# usbcan_20190426.net
KiCad netlist of a schematic drawn in EAGLE
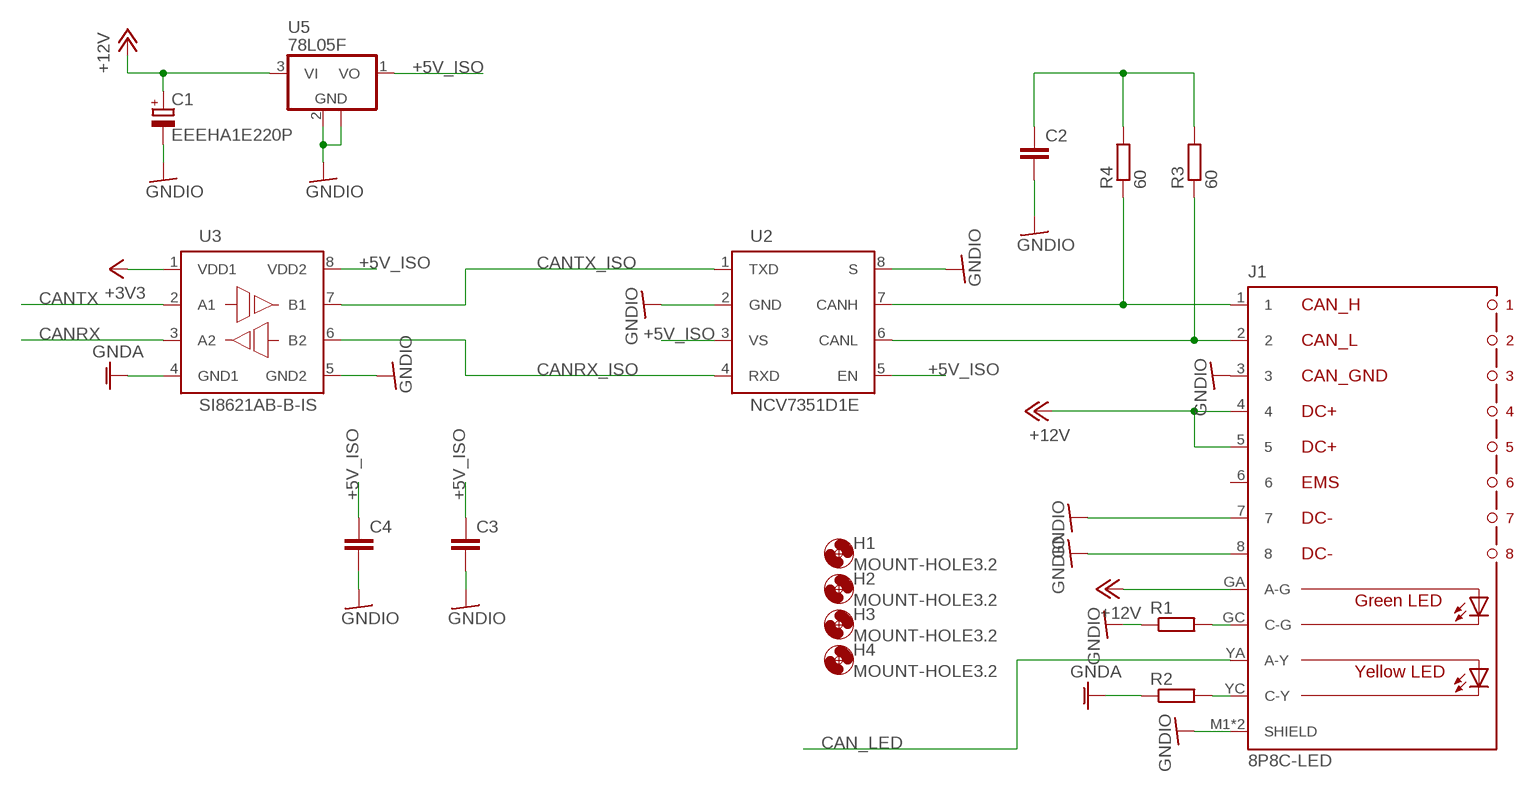
[diagram p0: schematic, sheet 1]
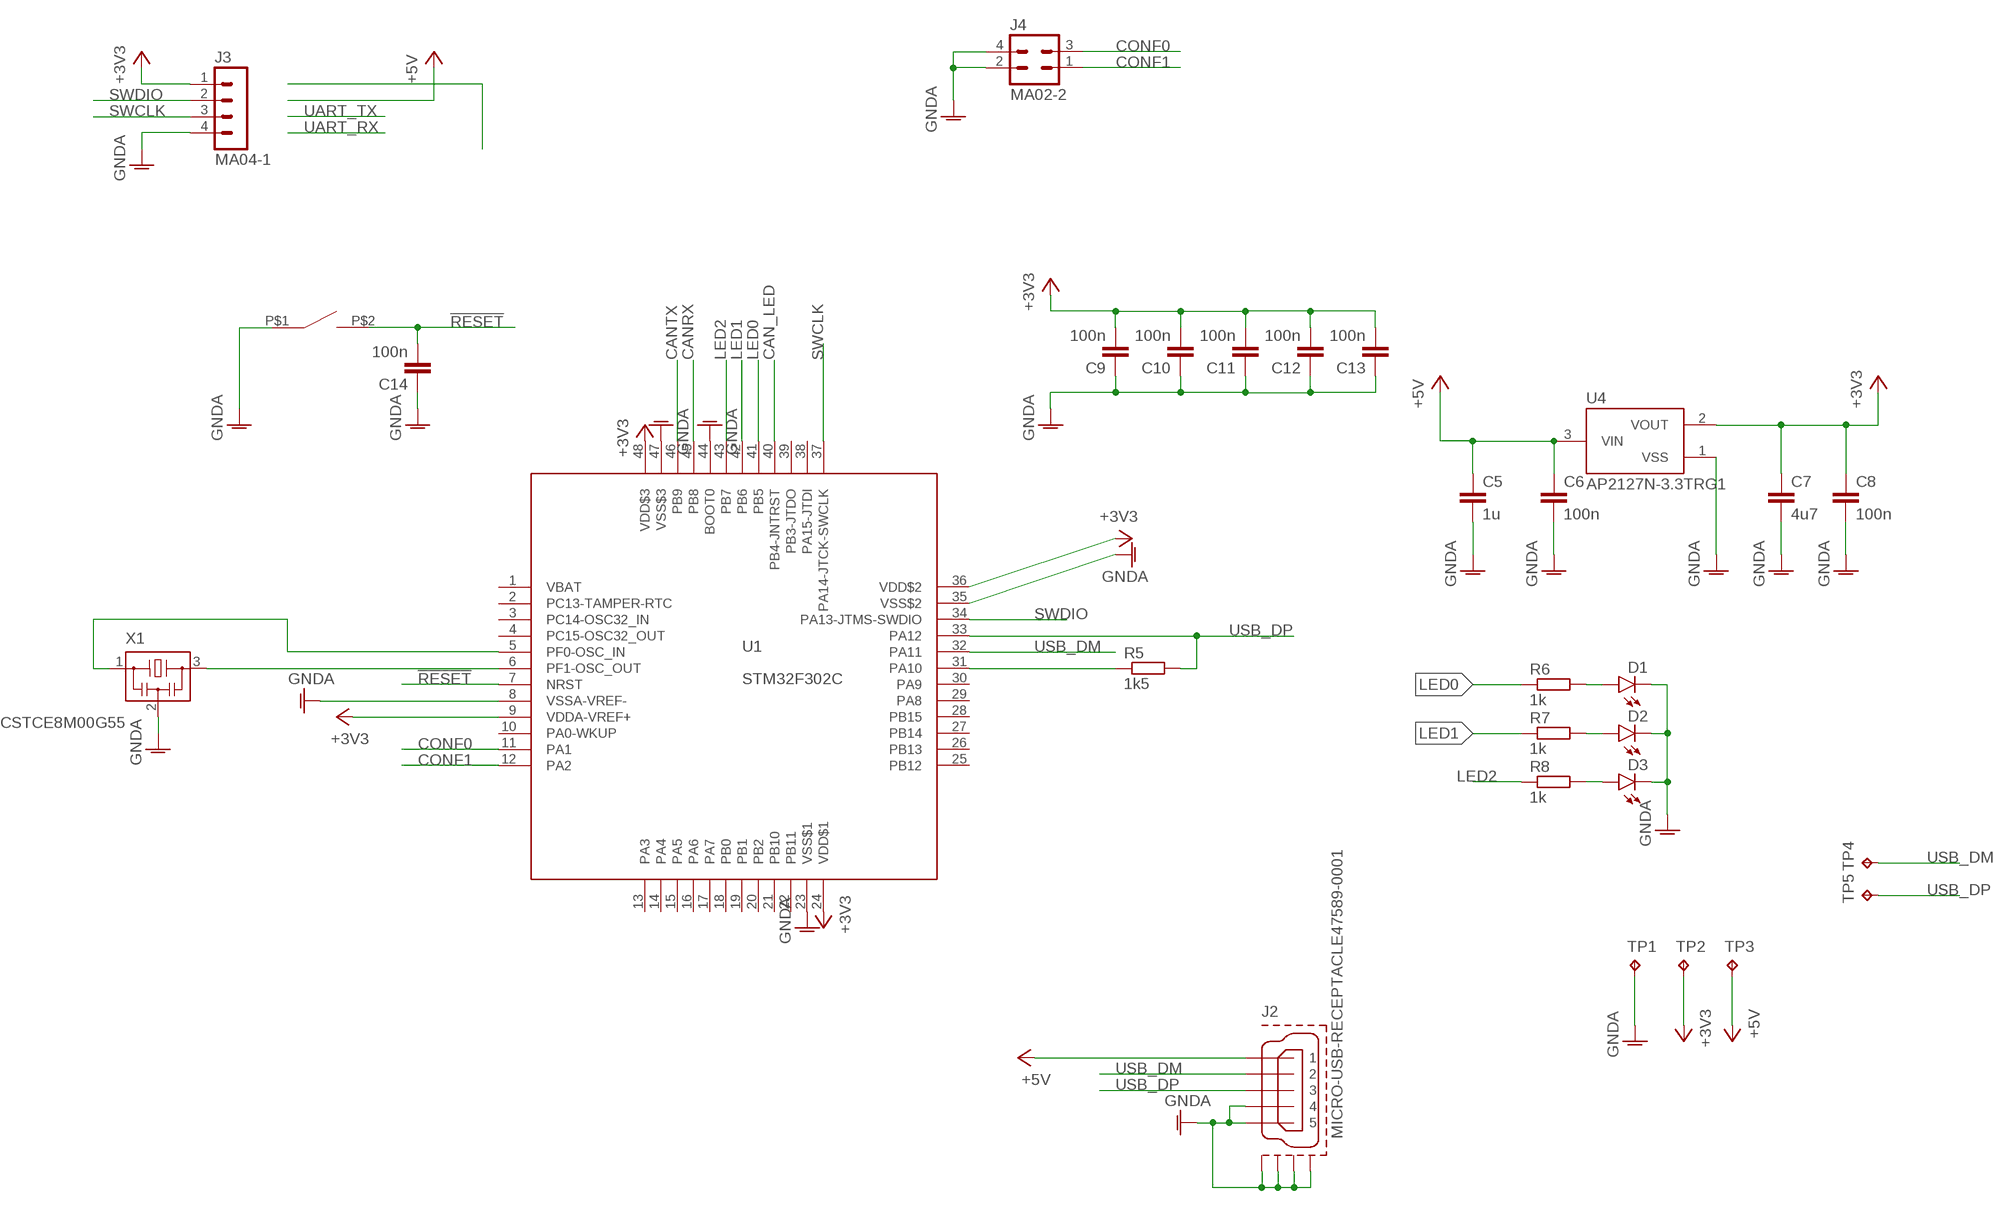
[diagram p1: schematic, sheet 2]

(export (version "E")
  (design (tool "Eeschema 10.0.6"))
  (components
    (comp (ref "C1")
      (value "EEEHA1E220P")
      (footprint "eagle-import:153CLV-0605")
      (libsource (lib "eagle-import") (part "CPOL-EU153CLV-0605"))
    )
    (comp (ref "C2")
      (value "C-EUC0603")
      (footprint "eagle-import:C0603")
      (libsource (lib "eagle-import") (part "rcl_334_C-EUC0603"))
    )
    (comp (ref "C3")
      (value "C-EUC0603")
      (footprint "eagle-import:C0603")
      (libsource (lib "eagle-import") (part "rcl_334_C-EUC0603"))
    )
    (comp (ref "C4")
      (value "C-EUC0603")
      (footprint "eagle-import:C0603")
      (libsource (lib "eagle-import") (part "rcl_334_C-EUC0603"))
    )
    (comp (ref "H1")
      (value "MOUNT-HOLE3.2")
      (footprint "eagle-import:3,2")
      (libsource (lib "eagle-import") (part "MOUNT-HOLE3.2"))
    )
    (comp (ref "H2")
      (value "MOUNT-HOLE3.2")
      (footprint "eagle-import:3,2")
      (libsource (lib "eagle-import") (part "MOUNT-HOLE3.2"))
    )
    (comp (ref "H3")
      (value "MOUNT-HOLE3.2")
      (footprint "eagle-import:3,2")
      (libsource (lib "eagle-import") (part "MOUNT-HOLE3.2"))
    )
    (comp (ref "H4")
      (value "MOUNT-HOLE3.2")
      (footprint "eagle-import:3,2")
      (libsource (lib "eagle-import") (part "MOUNT-HOLE3.2"))
    )
    (comp (ref "J1")
      (value "8P8C-LED")
      (footprint "eagle-import:8P8C-LED")
      (libsource (lib "eagle-import") (part "8P8C-LED"))
    )
    (comp (ref "R1")
      (value "R-EU_R0603")
      (footprint "eagle-import:R0603")
      (libsource (lib "eagle-import") (part "rcl_334_R-EU_R0603"))
    )
    (comp (ref "R2")
      (value "R-EU_R0603")
      (footprint "eagle-import:R0603")
      (libsource (lib "eagle-import") (part "rcl_334_R-EU_R0603"))
    )
    (comp (ref "R3")
      (value "60")
      (footprint "eagle-import:R0603")
      (libsource (lib "eagle-import") (part "rcl_334_R-EU_R0603"))
    )
    (comp (ref "R4")
      (value "60")
      (footprint "eagle-import:R0603")
      (libsource (lib "eagle-import") (part "rcl_334_R-EU_R0603"))
    )
    (comp (ref "U2")
      (value "NCV7351D1E")
      (footprint "eagle-import:SO08")
      (libsource (lib "eagle-import") (part "NCV7351D1E"))
    )
    (comp (ref "U3")
      (value "SI8621AB-B-IS")
      (footprint "eagle-import:SO08")
      (libsource (lib "eagle-import") (part "SI8621AB-B-IS"))
    )
    (comp (ref "U5")
      (value "78L05F")
      (footprint "eagle-import:SOT89")
      (libsource (lib "eagle-import") (part "78LF05"))
    )
    (comp (ref "C5")
      (value "1u")
      (footprint "eagle-import:C0603")
      (libsource (lib "eagle-import") (part "C-EUC0603"))
    )
    (comp (ref "C6")
      (value "100n")
      (footprint "eagle-import:C0603")
      (libsource (lib "eagle-import") (part "C-EUC0603"))
    )
    (comp (ref "C7")
      (value "4u7")
      (footprint "eagle-import:C0805")
      (libsource (lib "eagle-import") (part "C-EUC0805"))
    )
    (comp (ref "C8")
      (value "100n")
      (footprint "eagle-import:C0603")
      (libsource (lib "eagle-import") (part "C-EUC0603"))
    )
    (comp (ref "C9")
      (value "100n")
      (footprint "eagle-import:C0603")
      (libsource (lib "eagle-import") (part "C-EUC0603"))
    )
    (comp (ref "C10")
      (value "100n")
      (footprint "eagle-import:C0603")
      (libsource (lib "eagle-import") (part "C-EUC0603"))
    )
    (comp (ref "C11")
      (value "100n")
      (footprint "eagle-import:C0603")
      (libsource (lib "eagle-import") (part "C-EUC0603"))
    )
    (comp (ref "C12")
      (value "100n")
      (footprint "eagle-import:C0603")
      (libsource (lib "eagle-import") (part "C-EUC0603"))
    )
    (comp (ref "C13")
      (value "100n")
      (footprint "eagle-import:C0603")
      (libsource (lib "eagle-import") (part "C-EUC0603"))
    )
    (comp (ref "C14")
      (value "100n")
      (footprint "eagle-import:C0603")
      (libsource (lib "eagle-import") (part "C-EUC0603"))
    )
    (comp (ref "D1")
      (value "LEDCHIPLED_0805")
      (footprint "eagle-import:CHIPLED_0805")
      (libsource (lib "eagle-import") (part "LEDCHIPLED_0805"))
    )
    (comp (ref "D2")
      (value "LEDCHIPLED_0805")
      (footprint "eagle-import:CHIPLED_0805")
      (libsource (lib "eagle-import") (part "LEDCHIPLED_0805"))
    )
    (comp (ref "D3")
      (value "LEDCHIPLED_0805")
      (footprint "eagle-import:CHIPLED_0805")
      (libsource (lib "eagle-import") (part "LEDCHIPLED_0805"))
    )
    (comp (ref "J2")
      (value "MICRO-USB-RECEPTACLE47589-0001")
      (footprint "eagle-import:47589-0001")
      (libsource (lib "eagle-import") (part "MICRO-USB-RECEPTACLE47589-0001"))
    )
    (comp (ref "J3")
      (value "MA04-1")
      (footprint "eagle-import:MA04-1")
      (libsource (lib "eagle-import") (part "MA04-1"))
    )
    (comp (ref "J4")
      (value "MA02-2")
      (footprint "eagle-import:MA02-2W")
      (libsource (lib "eagle-import") (part "MA02-2"))
    )
    (comp (ref "R5")
      (value "1k5")
      (footprint "eagle-import:R0603")
      (libsource (lib "eagle-import") (part "R-EU_R0603"))
    )
    (comp (ref "R6")
      (value "1k")
      (footprint "eagle-import:R0603")
      (libsource (lib "eagle-import") (part "R-EU_R0603"))
    )
    (comp (ref "R7")
      (value "1k")
      (footprint "eagle-import:R0603")
      (libsource (lib "eagle-import") (part "R-EU_R0603"))
    )
    (comp (ref "R8")
      (value "1k")
      (footprint "eagle-import:R0603")
      (libsource (lib "eagle-import") (part "R-EU_R0603"))
    )
    (comp (ref "S1")
      (value "SWITCH_TACTILETOP")
      (footprint "eagle-import:SWITCH_TACTILE_3X6")
      (libsource (lib "eagle-import") (part "SWITCH_TACTILETOP"))
    )
    (comp (ref "TP1")
      (value "TPB1,27")
      (footprint "eagle-import:B1,27")
      (libsource (lib "eagle-import") (part "TPB1,27"))
    )
    (comp (ref "TP2")
      (value "TPB1,27")
      (footprint "eagle-import:B1,27")
      (libsource (lib "eagle-import") (part "TPB1,27"))
    )
    (comp (ref "TP3")
      (value "TPB1,27")
      (footprint "eagle-import:B1,27")
      (libsource (lib "eagle-import") (part "TPB1,27"))
    )
    (comp (ref "TP4")
      (value "TPB1,27")
      (footprint "eagle-import:B1,27")
      (libsource (lib "eagle-import") (part "TPB1,27"))
    )
    (comp (ref "TP5")
      (value "TPB1,27")
      (footprint "eagle-import:B1,27")
      (libsource (lib "eagle-import") (part "TPB1,27"))
    )
    (comp (ref "U1")
      (value "STM32F302C")
      (footprint "eagle-import:LQFP48")
      (libsource (lib "eagle-import") (part "STM32F303C"))
    )
    (comp (ref "U4")
      (value "AP2127N-3.3TRG1")
      (footprint "eagle-import:SOT95P240X110-3")
      (libsource (lib "eagle-import") (part "XC6206"))
    )
    (comp (ref "X1")
      (value "CSTCE8M00G55")
      (footprint "eagle-import:CSTCE8M00G55")
      (libsource (lib "eagle-import") (part "CSTCE8M00G55"))
    )
  )
  (nets
    (net (code "1") (name "+3V3") (class "Default")
      (node (ref "C10") (pin "2") (pinfunction "2_2") (pintype "passive"))
      (node (ref "C11") (pin "2") (pinfunction "2_2") (pintype "passive"))
      (node (ref "C12") (pin "2") (pinfunction "2_2") (pintype "passive"))
      (node (ref "C13") (pin "2") (pinfunction "2_2") (pintype "passive"))
      (node (ref "C7") (pin "1") (pinfunction "1_1") (pintype "passive"))
      (node (ref "C8") (pin "1") (pinfunction "1_1") (pintype "passive"))
      (node (ref "C9") (pin "2") (pinfunction "2_2") (pintype "passive"))
      (node (ref "J3") (pin "1") (pinfunction "1_1") (pintype "passive"))
      (node (ref "TP2") (pin "TP") (pinfunction "TP_TP") (pintype "input"))
      (node (ref "U1") (pin "24") (pinfunction "VDD$1_24") (pintype "passive"))
      (node (ref "U1") (pin "36") (pinfunction "VDD$2_36") (pintype "passive"))
      (node (ref "U1") (pin "48") (pinfunction "VDD$3_48") (pintype "passive"))
      (node (ref "U1") (pin "9") (pinfunction "VDDA-VREF+_9") (pintype "bidirectional"))
      (node (ref "U3") (pin "1") (pinfunction "VDD1_1") (pintype "power_in"))
      (node (ref "U4") (pin "2") (pinfunction "VOUT_2") (pintype "bidirectional"))
    )
    (net (code "2") (name "+5V") (class "Default")
      (node (ref "C5") (pin "1") (pinfunction "1_1") (pintype "passive"))
      (node (ref "C6") (pin "1") (pinfunction "1_1") (pintype "passive"))
      (node (ref "J2") (pin "1") (pinfunction "1_1") (pintype "input"))
      (node (ref "TP3") (pin "TP") (pinfunction "TP_TP") (pintype "input"))
      (node (ref "U4") (pin "3") (pinfunction "VIN_3") (pintype "bidirectional"))
    )
    (net (code "3") (name "+5V_ISO") (class "Default")
      (node (ref "C3") (pin "1") (pinfunction "1_1") (pintype "passive"))
      (node (ref "C4") (pin "1") (pinfunction "1_1") (pintype "passive"))
      (node (ref "U2") (pin "3") (pinfunction "VS_3") (pintype "power_in"))
      (node (ref "U2") (pin "5") (pinfunction "EN_5") (pintype "input"))
      (node (ref "U3") (pin "8") (pinfunction "VDD2_8") (pintype "power_in"))
      (node (ref "U5") (pin "1") (pinfunction "VO_1") (pintype "passive"))
    )
    (net (code "4") (name "+12V") (class "Default")
      (node (ref "C1") (pin "+") (pinfunction "+_+") (pintype "passive"))
      (node (ref "J1") (pin "4") (pinfunction "4_4") (pintype "input"))
      (node (ref "J1") (pin "5") (pinfunction "5_5") (pintype "input"))
      (node (ref "J1") (pin "GA") (pinfunction "A-G_GA") (pintype "passive"))
      (node (ref "U5") (pin "3") (pinfunction "VI_3") (pintype "input"))
    )
    (net (code "5") (name "CANRX") (class "Default")
      (node (ref "U1") (pin "45") (pinfunction "PB8_45") (pintype "bidirectional"))
      (node (ref "U3") (pin "3") (pinfunction "A2_3") (pintype "output"))
    )
    (net (code "6") (name "CANRX_ISO") (class "Default")
      (node (ref "U2") (pin "4") (pinfunction "RXD_4") (pintype "output"))
      (node (ref "U3") (pin "6") (pinfunction "B2_6") (pintype "output"))
    )
    (net (code "7") (name "CANTX") (class "Default")
      (node (ref "U1") (pin "46") (pinfunction "PB9_46") (pintype "bidirectional"))
      (node (ref "U3") (pin "2") (pinfunction "A1_2") (pintype "input"))
    )
    (net (code "8") (name "CANTX_ISO") (class "Default")
      (node (ref "U2") (pin "1") (pinfunction "TXD_1") (pintype "input"))
      (node (ref "U3") (pin "7") (pinfunction "B1_7") (pintype "output"))
    )
    (net (code "9") (name "CAN_LED") (class "Default")
      (node (ref "J1") (pin "YA") (pinfunction "A-Y_YA") (pintype "passive"))
      (node (ref "U1") (pin "40") (pinfunction "PB4-JNTRST_40") (pintype "bidirectional"))
    )
    (net (code "10") (name "CONF0") (class "Default")
      (node (ref "J4") (pin "3") (pinfunction "3_3") (pintype "passive"))
      (node (ref "U1") (pin "11") (pinfunction "PA1_11") (pintype "bidirectional"))
    )
    (net (code "11") (name "CONF1") (class "Default")
      (node (ref "J4") (pin "1") (pinfunction "1_1") (pintype "passive"))
      (node (ref "U1") (pin "12") (pinfunction "PA2_12") (pintype "bidirectional"))
    )
    (net (code "12") (name "GNDA") (class "Default")
      (node (ref "C10") (pin "1") (pinfunction "1_1") (pintype "passive"))
      (node (ref "C11") (pin "1") (pinfunction "1_1") (pintype "passive"))
      (node (ref "C12") (pin "1") (pinfunction "1_1") (pintype "passive"))
      (node (ref "C13") (pin "1") (pinfunction "1_1") (pintype "passive"))
      (node (ref "C14") (pin "1") (pinfunction "1_1") (pintype "passive"))
      (node (ref "C5") (pin "2") (pinfunction "2_2") (pintype "passive"))
      (node (ref "C6") (pin "2") (pinfunction "2_2") (pintype "passive"))
      (node (ref "C7") (pin "2") (pinfunction "2_2") (pintype "passive"))
      (node (ref "C8") (pin "2") (pinfunction "2_2") (pintype "passive"))
      (node (ref "C9") (pin "1") (pinfunction "1_1") (pintype "passive"))
      (node (ref "D1") (pin "C") (pinfunction "C_C") (pintype "passive"))
      (node (ref "D2") (pin "C") (pinfunction "C_C") (pintype "passive"))
      (node (ref "D3") (pin "C") (pinfunction "C_C") (pintype "passive"))
      (node (ref "J2") (pin "4") (pinfunction "4_4") (pintype "input"))
      (node (ref "J2") (pin "5") (pinfunction "5_5") (pintype "input"))
      (node (ref "J2") (pin "CASING1") (pinfunction "GND1_CASING1") (pintype "bidirectional"))
      (node (ref "J2") (pin "CASING2") (pinfunction "GND2_CASING2") (pintype "bidirectional"))
      (node (ref "J2") (pin "CASING3") (pinfunction "GND3_CASING3") (pintype "bidirectional"))
      (node (ref "J2") (pin "CASING4") (pinfunction "GND4_CASING4") (pintype "bidirectional"))
      (node (ref "J2") (pin "P$1") (pinfunction "GND1_P$1") (pintype "bidirectional"))
      (node (ref "J2") (pin "P$2") (pinfunction "GND1_P$2") (pintype "bidirectional"))
      (node (ref "J2") (pin "P$3") (pinfunction "GND2_P$3") (pintype "bidirectional"))
      (node (ref "J2") (pin "P$4") (pinfunction "GND2_P$4") (pintype "bidirectional"))
      (node (ref "J3") (pin "4") (pinfunction "4_4") (pintype "passive"))
      (node (ref "J4") (pin "2") (pinfunction "2_2") (pintype "passive"))
      (node (ref "J4") (pin "4") (pinfunction "4_4") (pintype "passive"))
      (node (ref "R2") (pin "1") (pinfunction "1_1") (pintype "passive"))
      (node (ref "S1") (pin "P$1") (pinfunction "1_P$1") (pintype "bidirectional"))
      (node (ref "TP1") (pin "TP") (pinfunction "TP_TP") (pintype "input"))
      (node (ref "U1") (pin "23") (pinfunction "VSS$1_23") (pintype "passive"))
      (node (ref "U1") (pin "35") (pinfunction "VSS$2_35") (pintype "passive"))
      (node (ref "U1") (pin "44") (pinfunction "BOOT0_44") (pintype "input"))
      (node (ref "U1") (pin "47") (pinfunction "VSS$3_47") (pintype "passive"))
      (node (ref "U1") (pin "8") (pinfunction "VSSA-VREF-_8") (pintype "bidirectional"))
      (node (ref "U3") (pin "4") (pinfunction "GND1_4") (pintype "power_in"))
      (node (ref "U4") (pin "1") (pinfunction "VSS_1") (pintype "bidirectional"))
      (node (ref "X1") (pin "2") (pinfunction "2_2") (pintype "passive"))
    )
    (net (code "13") (name "GNDIO") (class "Default")
      (node (ref "C1") (pin "-") (pinfunction "-_-") (pintype "passive"))
      (node (ref "C2") (pin "2") (pinfunction "2_2") (pintype "passive"))
      (node (ref "C3") (pin "2") (pinfunction "2_2") (pintype "passive"))
      (node (ref "C4") (pin "2") (pinfunction "2_2") (pintype "passive"))
      (node (ref "J1") (pin "3") (pinfunction "3_3") (pintype "input"))
      (node (ref "J1") (pin "7") (pinfunction "7_7") (pintype "input"))
      (node (ref "J1") (pin "8") (pinfunction "8_8") (pintype "input"))
      (node (ref "J1") (pin "M1") (pinfunction "SHIELD_M1") (pintype "passive"))
      (node (ref "J1") (pin "M2") (pinfunction "SHIELD_M2") (pintype "passive"))
      (node (ref "R1") (pin "1") (pinfunction "1_1") (pintype "passive"))
      (node (ref "U2") (pin "2") (pinfunction "GND_2") (pintype "power_in"))
      (node (ref "U2") (pin "8") (pinfunction "S_8") (pintype "input"))
      (node (ref "U3") (pin "5") (pinfunction "GND2_5") (pintype "power_in"))
      (node (ref "U5") (pin "2") (pinfunction "GND_2") (pintype "passive"))
      (node (ref "U5") (pin "2@1") (pinfunction "GND_2@1") (pintype "passive"))
    )
    (net (code "14") (name "LED0") (class "Default")
      (node (ref "R6") (pin "1") (pinfunction "1_1") (pintype "passive"))
      (node (ref "U1") (pin "41") (pinfunction "PB5_41") (pintype "bidirectional"))
    )
    (net (code "15") (name "LED1") (class "Default")
      (node (ref "R7") (pin "1") (pinfunction "1_1") (pintype "passive"))
      (node (ref "U1") (pin "42") (pinfunction "PB6_42") (pintype "bidirectional"))
    )
    (net (code "16") (name "LED2") (class "Default")
      (node (ref "R8") (pin "1") (pinfunction "1_1") (pintype "passive"))
      (node (ref "U1") (pin "43") (pinfunction "PB7_43") (pintype "bidirectional"))
    )
    (net (code "17") (name "Net-(C2-Pad1)") (class "Default")
      (node (ref "C2") (pin "1") (pinfunction "1_1") (pintype "passive"))
      (node (ref "R3") (pin "2") (pinfunction "2_2") (pintype "passive"))
      (node (ref "R4") (pin "2") (pinfunction "2_2") (pintype "passive"))
    )
    (net (code "18") (name "Net-(D1-PadA)") (class "Default")
      (node (ref "D1") (pin "A") (pinfunction "A_A") (pintype "passive"))
      (node (ref "R6") (pin "2") (pinfunction "2_2") (pintype "passive"))
    )
    (net (code "19") (name "Net-(D2-PadA)") (class "Default")
      (node (ref "D2") (pin "A") (pinfunction "A_A") (pintype "passive"))
      (node (ref "R7") (pin "2") (pinfunction "2_2") (pintype "passive"))
    )
    (net (code "20") (name "Net-(D3-PadA)") (class "Default")
      (node (ref "D3") (pin "A") (pinfunction "A_A") (pintype "passive"))
      (node (ref "R8") (pin "2") (pinfunction "2_2") (pintype "passive"))
    )
    (net (code "21") (name "Net-(J1-C-G)") (class "Default")
      (node (ref "J1") (pin "GC") (pinfunction "C-G_GC") (pintype "passive"))
      (node (ref "R1") (pin "2") (pinfunction "2_2") (pintype "passive"))
    )
    (net (code "22") (name "Net-(J1-C-Y)") (class "Default")
      (node (ref "J1") (pin "YC") (pinfunction "C-Y_YC") (pintype "passive"))
      (node (ref "R2") (pin "2") (pinfunction "2_2") (pintype "passive"))
    )
    (net (code "23") (name "Net-(U1-PA10)") (class "Default")
      (node (ref "R5") (pin "1") (pinfunction "1_1") (pintype "passive"))
      (node (ref "U1") (pin "31") (pinfunction "PA10_31") (pintype "bidirectional"))
    )
    (net (code "24") (name "Net-(U1-PF0-OSC_IN)") (class "Default")
      (node (ref "U1") (pin "5") (pinfunction "PF0-OSC_IN_5") (pintype "input"))
      (node (ref "X1") (pin "1") (pinfunction "1_1") (pintype "passive"))
    )
    (net (code "25") (name "Net-(U1-PF1-OSC_OUT)") (class "Default")
      (node (ref "U1") (pin "6") (pinfunction "PF1-OSC_OUT_6") (pintype "output"))
      (node (ref "X1") (pin "3") (pinfunction "3_3") (pintype "passive"))
    )
    (net (code "26") (name "Net-(U2-CANH)") (class "Default")
      (node (ref "J1") (pin "1") (pinfunction "1_1") (pintype "input"))
      (node (ref "R4") (pin "1") (pinfunction "1_1") (pintype "passive"))
      (node (ref "U2") (pin "7") (pinfunction "CANH_7") (pintype "output"))
    )
    (net (code "27") (name "Net-(U2-CANL)") (class "Default")
      (node (ref "J1") (pin "2") (pinfunction "2_2") (pintype "input"))
      (node (ref "R3") (pin "1") (pinfunction "1_1") (pintype "passive"))
      (node (ref "U2") (pin "6") (pinfunction "CANL_6") (pintype "output"))
    )
    (net (code "28") (name "SWCLK") (class "Default")
      (node (ref "J3") (pin "3") (pinfunction "3_3") (pintype "passive"))
      (node (ref "U1") (pin "37") (pinfunction "PA14-JTCK-SWCLK_37") (pintype "bidirectional"))
    )
    (net (code "29") (name "SWDIO") (class "Default")
      (node (ref "J3") (pin "2") (pinfunction "2_2") (pintype "passive"))
      (node (ref "U1") (pin "34") (pinfunction "PA13-JTMS-SWDIO_34") (pintype "bidirectional"))
    )
    (net (code "32") (name "USB_DM") (class "Default")
      (node (ref "J2") (pin "2") (pinfunction "2_2") (pintype "input"))
      (node (ref "TP4") (pin "TP") (pinfunction "TP_TP") (pintype "input"))
      (node (ref "U1") (pin "32") (pinfunction "PA11_32") (pintype "bidirectional"))
    )
    (net (code "33") (name "USB_DP") (class "Default")
      (node (ref "J2") (pin "3") (pinfunction "3_3") (pintype "input"))
      (node (ref "R5") (pin "2") (pinfunction "2_2") (pintype "passive"))
      (node (ref "TP5") (pin "TP") (pinfunction "TP_TP") (pintype "input"))
      (node (ref "U1") (pin "33") (pinfunction "PA12_33") (pintype "bidirectional"))
    )
    (net (code "34") (name "unconnected-(J1-Pad6)") (class "Default")
      (node (ref "J1") (pin "6") (pinfunction "6_6") (pintype "input"))
    )
    (net (code "35") (name "unconnected-(U1-PA0-WKUP-Pad10)") (class "Default")
      (node (ref "U1") (pin "10") (pinfunction "PA0-WKUP_10") (pintype "bidirectional"))
    )
    (net (code "36") (name "unconnected-(U1-PA3-Pad13)") (class "Default")
      (node (ref "U1") (pin "13") (pinfunction "PA3_13") (pintype "bidirectional"))
    )
    (net (code "37") (name "unconnected-(U1-PA4-Pad14)") (class "Default")
      (node (ref "U1") (pin "14") (pinfunction "PA4_14") (pintype "bidirectional"))
    )
    (net (code "38") (name "unconnected-(U1-PA5-Pad15)") (class "Default")
      (node (ref "U1") (pin "15") (pinfunction "PA5_15") (pintype "bidirectional"))
    )
    (net (code "39") (name "unconnected-(U1-PA6-Pad16)") (class "Default")
      (node (ref "U1") (pin "16") (pinfunction "PA6_16") (pintype "bidirectional"))
    )
    (net (code "40") (name "unconnected-(U1-PA7-Pad17)") (class "Default")
      (node (ref "U1") (pin "17") (pinfunction "PA7_17") (pintype "bidirectional"))
    )
    (net (code "41") (name "unconnected-(U1-PA8-Pad29)") (class "Default")
      (node (ref "U1") (pin "29") (pinfunction "PA8_29") (pintype "bidirectional"))
    )
    (net (code "42") (name "unconnected-(U1-PA9-Pad30)") (class "Default")
      (node (ref "U1") (pin "30") (pinfunction "PA9_30") (pintype "bidirectional"))
    )
    (net (code "43") (name "unconnected-(U1-PA15-JTDI-Pad38)") (class "Default")
      (node (ref "U1") (pin "38") (pinfunction "PA15-JTDI_38") (pintype "bidirectional"))
    )
    (net (code "44") (name "unconnected-(U1-PB0-Pad18)") (class "Default")
      (node (ref "U1") (pin "18") (pinfunction "PB0_18") (pintype "bidirectional"))
    )
    (net (code "45") (name "unconnected-(U1-PB1-Pad19)") (class "Default")
      (node (ref "U1") (pin "19") (pinfunction "PB1_19") (pintype "bidirectional"))
    )
    (net (code "46") (name "unconnected-(U1-PB2-Pad20)") (class "Default")
      (node (ref "U1") (pin "20") (pinfunction "PB2_20") (pintype "bidirectional"))
    )
    (net (code "47") (name "unconnected-(U1-PB3-JTDO-Pad39)") (class "Default")
      (node (ref "U1") (pin "39") (pinfunction "PB3-JTDO_39") (pintype "bidirectional"))
    )
    (net (code "48") (name "unconnected-(U1-PB10-Pad21)") (class "Default")
      (node (ref "U1") (pin "21") (pinfunction "PB10_21") (pintype "bidirectional"))
    )
    (net (code "49") (name "unconnected-(U1-PB11-Pad22)") (class "Default")
      (node (ref "U1") (pin "22") (pinfunction "PB11_22") (pintype "bidirectional"))
    )
    (net (code "50") (name "unconnected-(U1-PB12-Pad25)") (class "Default")
      (node (ref "U1") (pin "25") (pinfunction "PB12_25") (pintype "bidirectional"))
    )
    (net (code "51") (name "unconnected-(U1-PB13-Pad26)") (class "Default")
      (node (ref "U1") (pin "26") (pinfunction "PB13_26") (pintype "bidirectional"))
    )
    (net (code "52") (name "unconnected-(U1-PB14-Pad27)") (class "Default")
      (node (ref "U1") (pin "27") (pinfunction "PB14_27") (pintype "bidirectional"))
    )
    (net (code "53") (name "unconnected-(U1-PB15-Pad28)") (class "Default")
      (node (ref "U1") (pin "28") (pinfunction "PB15_28") (pintype "bidirectional"))
    )
    (net (code "54") (name "unconnected-(U1-PC13-TAMPER-RTC-Pad2)") (class "Default")
      (node (ref "U1") (pin "2") (pinfunction "PC13-TAMPER-RTC_2") (pintype "bidirectional"))
    )
    (net (code "55") (name "unconnected-(U1-PC14-OSC32_IN-Pad3)") (class "Default")
      (node (ref "U1") (pin "3") (pinfunction "PC14-OSC32_IN_3") (pintype "bidirectional"))
    )
    (net (code "56") (name "unconnected-(U1-PC15-OSC32_OUT-Pad4)") (class "Default")
      (node (ref "U1") (pin "4") (pinfunction "PC15-OSC32_OUT_4") (pintype "bidirectional"))
    )
    (net (code "57") (name "unconnected-(U1-VBAT-Pad1)") (class "Default")
      (node (ref "U1") (pin "1") (pinfunction "VBAT_1") (pintype "passive"))
    )
    (net (code "58") (name "~{RESET}") (class "Default")
      (node (ref "C14") (pin "2") (pinfunction "2_2") (pintype "passive"))
      (node (ref "S1") (pin "P$2") (pinfunction "2_P$2") (pintype "bidirectional"))
      (node (ref "U1") (pin "7") (pinfunction "NRST_7") (pintype "bidirectional"))
    )
  )
)
